# SCH_slime-vr.net
KiCad netlist of a schematic drawn in EasyEDA
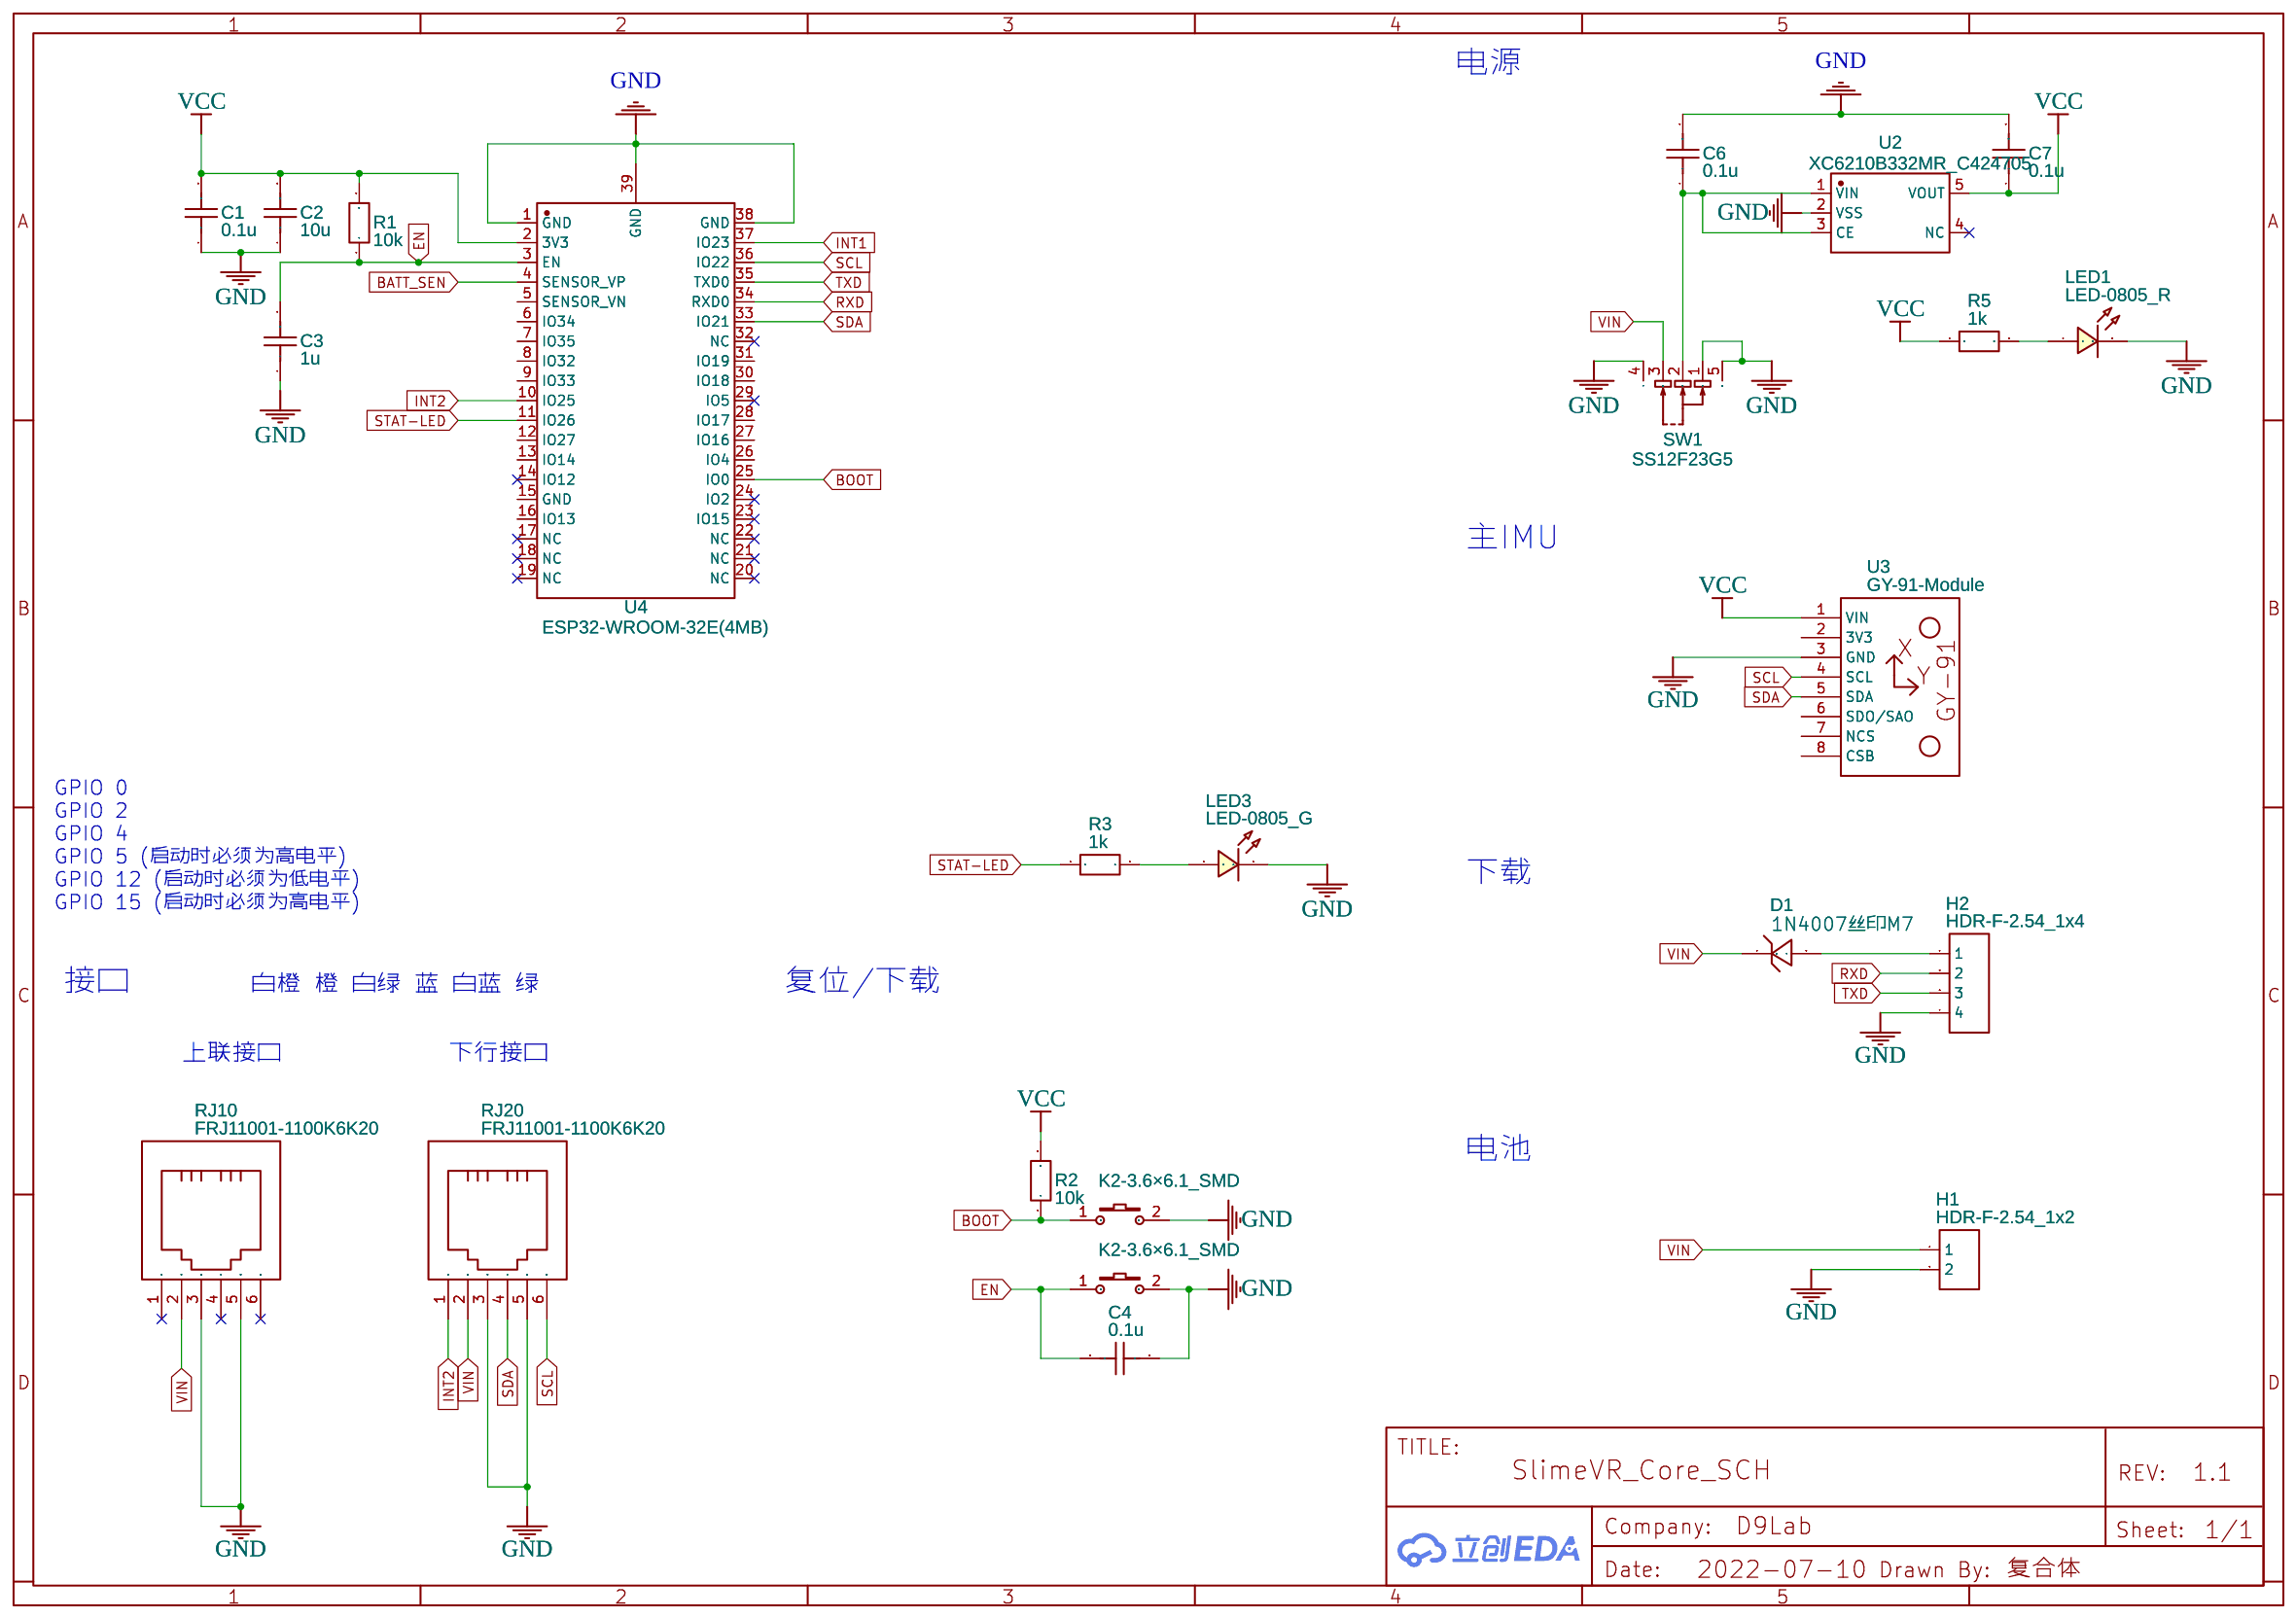
[diagram p0: SlimeVR_Core_SCH]
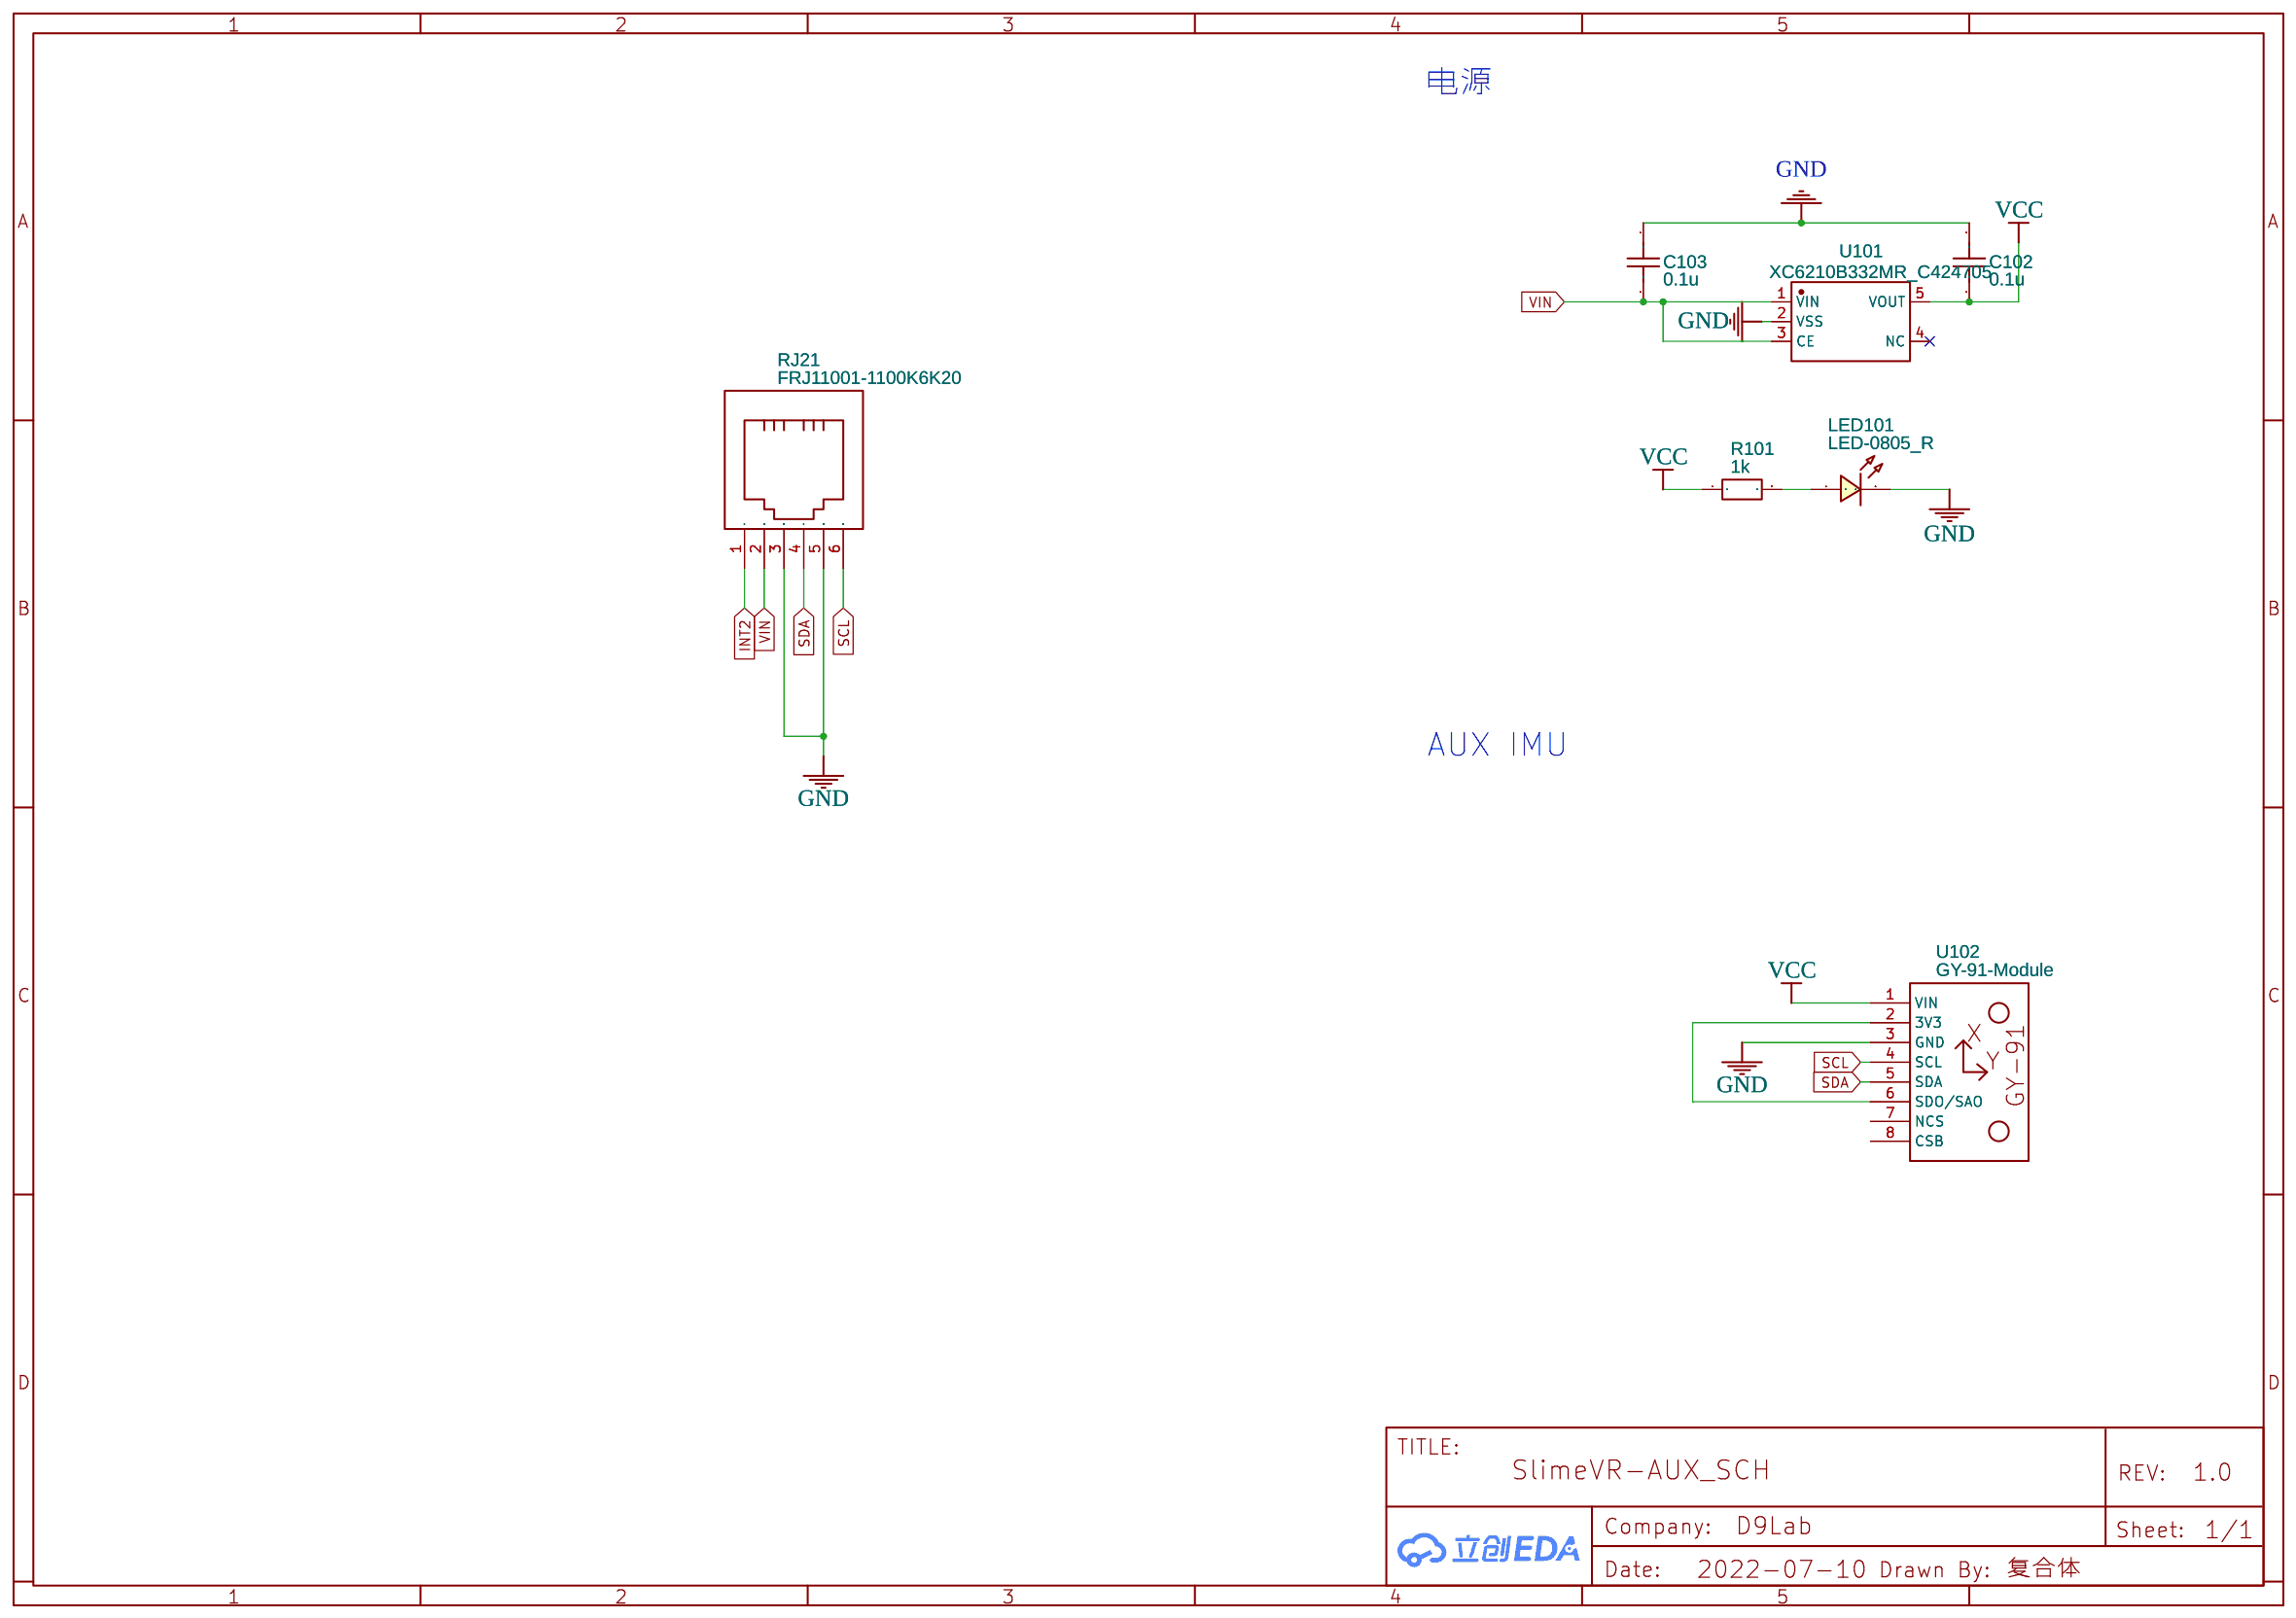
[diagram p1: SlimeVR-AUX_SCH]

(export (version "E")
  (design (tool "Eeschema 10.0.6"))
  (components
    (comp (ref "C1") (value "0.1u") (libsource (lib "") (part "C_0805_US_1")))
    (comp (ref "C2") (value "10u") (libsource (lib "") (part "C_0805_US_1")))
    (comp (ref "C3") (value "1u") (libsource (lib "") (part "C_0805_US_1")))
    (comp (ref "C4") (value "0.1u") (libsource (lib "") (part "C_0805_US")))
    (comp (ref "C6") (value "0.1u") (libsource (lib "") (part "C_0805_US_1")))
    (comp (ref "C7") (value "0.1u") (libsource (lib "") (part "C_0805_US_1")))
    (comp (ref "D1")
      (value "1N4007丝印M7")
      (fields (field (name "BOM_Supplier Part") "C9900013679"))
      (libsource (lib "") (part "1N4007丝印M7"))
    )
    (comp (ref "DL")
      (value "K2-3.6×6.1_SMD")
      (fields
        (field (name "BOM_Manufacturer Part") "K2-1107ST-A4SW-06")
        (field (name "BOM_Supplier Part") "C118141")
      )
      (libsource (lib "") (part "K2-3.6×6.1_SMD_1"))
    )
    (comp (ref "EN")
      (value "K2-3.6×6.1_SMD")
      (fields
        (field (name "BOM_Manufacturer Part") "K2-1107ST-A4SW-06")
        (field (name "BOM_Supplier Part") "C118141")
      )
      (libsource (lib "") (part "K2-3.6×6.1_SMD"))
    )
    (comp (ref "H1")
      (value "HDR-F-2.54_1x2")
      (fields (field (name "BOM_Supplier Part") "C49661"))
      (libsource (lib "") (part "HDR-F-2.54_1x2"))
    )
    (comp (ref "H2")
      (value "HDR-F-2.54_1x4")
      (fields (field (name "BOM_Supplier Part") "C225501"))
      (libsource (lib "") (part "HDR-F-2.54_1x4"))
    )
    (comp (ref "LED1")
      (value "LED-0805_R")
      (fields
        (field (name "BOM_Manufacturer Part") "17-21SURC/S530-A3/TR8")
        (field (name "BOM_Supplier Part") "C72037")
      )
      (libsource (lib "") (part "LED-0805_R"))
    )
    (comp (ref "LED3")
      (value "LED-0805_G")
      (fields (field (name "BOM_Manufacturer Part") "NCD0805G1") (field (name "BOM_Supplier Part") "C84260"))
      (libsource (lib "") (part "LED-0805_G"))
    )
    (comp (ref "R1") (value "10k") (libsource (lib "") (part "R_0805_EU")))
    (comp (ref "R2") (value "10k") (libsource (lib "") (part "R_0805_EU")))
    (comp (ref "R3") (value "1k") (libsource (lib "") (part "R_0805_EU_1")))
    (comp (ref "R5") (value "1k") (libsource (lib "") (part "R_0805_EU_1")))
    (comp (ref "RJ10")
      (value "FRJ11001-1100K6K20")
      (fields (field (name "BOM_Supplier Part") "C456393"))
      (libsource (lib "") (part "FRJ11001-1100K6K20"))
    )
    (comp (ref "RJ20")
      (value "FRJ11001-1100K6K20")
      (fields (field (name "BOM_Supplier Part") "C456393"))
      (libsource (lib "") (part "FRJ11001-1100K6K20"))
    )
    (comp (ref "SW1")
      (value "SS12F23G5")
      (fields (field (name "BOM_Supplier Part") "C2887262"))
      (libsource (lib "") (part "SS12F23G5"))
    )
    (comp (ref "U2")
      (value "XC6210B332MR_C424705")
      (fields
        (field (name "BOM_Manufacturer Part") "XC6210B332MR")
        (field (name "BOM_Supplier Part") "C424705")
      )
      (libsource (lib "") (part "XC6210B332MR_C424705"))
    )
    (comp (ref "U3")
      (value "GY-91-Module")
      (fields (field (name "BOM_Manufacturer Part") "GY-91 MPU9250 + BMP280"))
      (libsource (lib "") (part "GY-91-Module"))
    )
    (comp (ref "U4")
      (value "ESP32-WROOM-32E(4MB)")
      (fields (field (name "BOM_Supplier Part") "C701341"))
      (libsource (lib "") (part "ESP32-WROOM-32E(4MB)"))
    )
    (comp (ref "C102") (value "0.1u") (libsource (lib "") (part "C_0805_US")))
    (comp (ref "C103") (value "0.1u") (libsource (lib "") (part "C_0805_US")))
    (comp (ref "LED101")
      (value "LED-0805_R")
      (fields
        (field (name "BOM_Manufacturer Part") "17-21SURC/S530-A3/TR8")
        (field (name "BOM_Supplier Part") "C72037")
      )
      (libsource (lib "") (part "LED-0805_R"))
    )
    (comp (ref "R101") (value "1k") (libsource (lib "") (part "R_0805_EU")))
    (comp (ref "RJ21")
      (value "FRJ11001-1100K6K20")
      (fields (field (name "BOM_Supplier Part") "C456393"))
      (libsource (lib "") (part "FRJ11001-1100K6K20"))
    )
    (comp (ref "U101")
      (value "XC6210B332MR_C424705")
      (fields
        (field (name "BOM_Manufacturer Part") "XC6210B332MR")
        (field (name "BOM_Supplier Part") "C424705")
      )
      (libsource (lib "") (part "XC6210B332MR_C424705"))
    )
    (comp (ref "U102")
      (value "GY-91-Module")
      (fields (field (name "BOM_Manufacturer Part") "GY-91 MPU9250 + BMP280"))
      (libsource (lib "") (part "GY-91-Module"))
    )
  )
  (nets
    (net (code "1") (name "BATT_SEN") (class "Default")
      (node (ref "U4") (pin "4") (pinfunction "SENSOR_VP_4") (pintype "unspecified"))
    )
    (net (code "2") (name "BOOT") (class "Default")
      (node (ref "DL") (pin "1") (pinfunction "1_1") (pintype "unspecified"))
      (node (ref "R2") (pin "1") (pinfunction "1_1") (pintype "unspecified"))
      (node (ref "U4") (pin "25") (pinfunction "IO0_25") (pintype "unspecified"))
    )
    (net (code "3") (name "EN") (class "Default")
      (node (ref "C3") (pin "2") (pinfunction "2_2") (pintype "unspecified"))
      (node (ref "C4") (pin "2") (pinfunction "2_2") (pintype "unspecified"))
      (node (ref "EN") (pin "1") (pinfunction "1_1") (pintype "unspecified"))
      (node (ref "R1") (pin "1") (pinfunction "1_1") (pintype "unspecified"))
      (node (ref "U4") (pin "3") (pinfunction "EN_3") (pintype "unspecified"))
    )
    (net (code "4") (name "GND") (class "Default")
      (node (ref "C1") (pin "1") (pinfunction "1_1") (pintype "unspecified"))
      (node (ref "C102") (pin "2") (pinfunction "2_2") (pintype "unspecified"))
      (node (ref "C103") (pin "2") (pinfunction "2_2") (pintype "unspecified"))
      (node (ref "C2") (pin "1") (pinfunction "1_1") (pintype "unspecified"))
      (node (ref "C3") (pin "1") (pinfunction "1_1") (pintype "unspecified"))
      (node (ref "C4") (pin "1") (pinfunction "1_1") (pintype "unspecified"))
      (node (ref "C6") (pin "2") (pinfunction "2_2") (pintype "unspecified"))
      (node (ref "C7") (pin "2") (pinfunction "2_2") (pintype "unspecified"))
      (node (ref "DL") (pin "2") (pinfunction "2_2") (pintype "unspecified"))
      (node (ref "EN") (pin "2") (pinfunction "2_2") (pintype "unspecified"))
      (node (ref "H1") (pin "2") (pinfunction "2_2") (pintype "input"))
      (node (ref "H2") (pin "4") (pinfunction "4_4") (pintype "unspecified"))
      (node (ref "LED1") (pin "2") (pinfunction "2_2") (pintype "unspecified"))
      (node (ref "LED101") (pin "2") (pinfunction "2_2") (pintype "unspecified"))
      (node (ref "LED3") (pin "2") (pinfunction "2_2") (pintype "unspecified"))
      (node (ref "RJ10") (pin "3") (pinfunction "3_3") (pintype "unspecified"))
      (node (ref "RJ10") (pin "5") (pinfunction "5_5") (pintype "unspecified"))
      (node (ref "RJ20") (pin "3") (pinfunction "3_3") (pintype "unspecified"))
      (node (ref "RJ20") (pin "5") (pinfunction "5_5") (pintype "unspecified"))
      (node (ref "RJ21") (pin "3") (pinfunction "3_3") (pintype "unspecified"))
      (node (ref "RJ21") (pin "5") (pinfunction "5_5") (pintype "unspecified"))
      (node (ref "SW1") (pin "1") (pinfunction "1_1") (pintype "unspecified"))
      (node (ref "SW1") (pin "4") (pinfunction "4_4") (pintype "unspecified"))
      (node (ref "SW1") (pin "5") (pinfunction "5_5") (pintype "unspecified"))
      (node (ref "U101") (pin "2") (pinfunction "VSS_2") (pintype "unspecified"))
      (node (ref "U102") (pin "3") (pinfunction "GND_3") (pintype "unspecified"))
      (node (ref "U2") (pin "2") (pinfunction "VSS_2") (pintype "unspecified"))
      (node (ref "U3") (pin "3") (pinfunction "GND_3") (pintype "unspecified"))
      (node (ref "U4") (pin "1") (pinfunction "GND_1") (pintype "unspecified"))
      (node (ref "U4") (pin "38") (pinfunction "GND_38") (pintype "unspecified"))
      (node (ref "U4") (pin "39") (pinfunction "GND_39") (pintype "unspecified"))
    )
    (net (code "5") (name "INT1") (class "Default")
      (node (ref "U4") (pin "37") (pinfunction "IO23_37") (pintype "unspecified"))
    )
    (net (code "6") (name "INT2") (class "Default")
      (node (ref "RJ20") (pin "1") (pinfunction "1_1") (pintype "unspecified"))
      (node (ref "RJ21") (pin "1") (pinfunction "1_1") (pintype "unspecified"))
      (node (ref "U4") (pin "10") (pinfunction "IO25_10") (pintype "unspecified"))
    )
    (net (code "7") (name "Net-(D1-A)") (class "Default")
      (node (ref "D1") (pin "2") (pinfunction "A_2") (pintype "unspecified"))
      (node (ref "H2") (pin "1") (pinfunction "1_1") (pintype "unspecified"))
    )
    (net (code "8") (name "Net-(LED1-Pad1)") (class "Default")
      (node (ref "LED1") (pin "1") (pinfunction "1_1") (pintype "unspecified"))
      (node (ref "R5") (pin "2") (pinfunction "2_2") (pintype "unspecified"))
    )
    (net (code "9") (name "Net-(LED3-Pad1)") (class "Default")
      (node (ref "LED3") (pin "1") (pinfunction "1_1") (pintype "unspecified"))
      (node (ref "R3") (pin "2") (pinfunction "2_2") (pintype "unspecified"))
    )
    (net (code "10") (name "Net-(LED101-Pad1)") (class "Default")
      (node (ref "LED101") (pin "1") (pinfunction "1_1") (pintype "unspecified"))
      (node (ref "R101") (pin "2") (pinfunction "2_2") (pintype "unspecified"))
    )
    (net (code "11") (name "Net-(U2-CE)") (class "Default")
      (node (ref "C6") (pin "1") (pinfunction "1_1") (pintype "unspecified"))
      (node (ref "SW1") (pin "2") (pinfunction "2_2") (pintype "unspecified"))
      (node (ref "U2") (pin "1") (pinfunction "VIN_1") (pintype "unspecified"))
      (node (ref "U2") (pin "3") (pinfunction "CE_3") (pintype "unspecified"))
    )
    (net (code "12") (name "Net-(U102-3V3)") (class "Default")
      (node (ref "U102") (pin "2") (pinfunction "3V3_2") (pintype "unspecified"))
      (node (ref "U102") (pin "6") (pinfunction "SDO/SAO_6") (pintype "unspecified"))
    )
    (net (code "13") (name "RXD") (class "Default")
      (node (ref "H2") (pin "2") (pinfunction "2_2") (pintype "unspecified"))
      (node (ref "U4") (pin "34") (pinfunction "RXD0_34") (pintype "unspecified"))
    )
    (net (code "14") (name "SCL") (class "Default")
      (node (ref "RJ20") (pin "6") (pinfunction "6_6") (pintype "unspecified"))
      (node (ref "RJ21") (pin "6") (pinfunction "6_6") (pintype "unspecified"))
      (node (ref "U102") (pin "4") (pinfunction "SCL_4") (pintype "unspecified"))
      (node (ref "U3") (pin "4") (pinfunction "SCL_4") (pintype "unspecified"))
      (node (ref "U4") (pin "36") (pinfunction "IO22_36") (pintype "unspecified"))
    )
    (net (code "15") (name "SDA") (class "Default")
      (node (ref "RJ20") (pin "4") (pinfunction "4_4") (pintype "unspecified"))
      (node (ref "RJ21") (pin "4") (pinfunction "4_4") (pintype "unspecified"))
      (node (ref "U102") (pin "5") (pinfunction "SDA_5") (pintype "unspecified"))
      (node (ref "U3") (pin "5") (pinfunction "SDA_5") (pintype "unspecified"))
      (node (ref "U4") (pin "33") (pinfunction "IO21_33") (pintype "unspecified"))
    )
    (net (code "16") (name "STAT-LED") (class "Default")
      (node (ref "R3") (pin "1") (pinfunction "1_1") (pintype "unspecified"))
      (node (ref "U4") (pin "11") (pinfunction "IO26_11") (pintype "unspecified"))
    )
    (net (code "17") (name "TXD") (class "Default")
      (node (ref "H2") (pin "3") (pinfunction "3_3") (pintype "unspecified"))
      (node (ref "U4") (pin "35") (pinfunction "TXD0_35") (pintype "unspecified"))
    )
    (net (code "18") (name "VCC") (class "Default")
      (node (ref "C1") (pin "2") (pinfunction "2_2") (pintype "unspecified"))
      (node (ref "C102") (pin "1") (pinfunction "1_1") (pintype "unspecified"))
      (node (ref "C2") (pin "2") (pinfunction "2_2") (pintype "unspecified"))
      (node (ref "C7") (pin "1") (pinfunction "1_1") (pintype "unspecified"))
      (node (ref "R1") (pin "2") (pinfunction "2_2") (pintype "unspecified"))
      (node (ref "R101") (pin "1") (pinfunction "1_1") (pintype "unspecified"))
      (node (ref "R2") (pin "2") (pinfunction "2_2") (pintype "unspecified"))
      (node (ref "R5") (pin "1") (pinfunction "1_1") (pintype "unspecified"))
      (node (ref "U101") (pin "5") (pinfunction "VOUT_5") (pintype "unspecified"))
      (node (ref "U102") (pin "1") (pinfunction "VIN_1") (pintype "unspecified"))
      (node (ref "U2") (pin "5") (pinfunction "VOUT_5") (pintype "unspecified"))
      (node (ref "U3") (pin "1") (pinfunction "VIN_1") (pintype "unspecified"))
      (node (ref "U4") (pin "2") (pinfunction "3V3_2") (pintype "unspecified"))
    )
    (net (code "19") (name "VIN") (class "Default")
      (node (ref "C103") (pin "1") (pinfunction "1_1") (pintype "unspecified"))
      (node (ref "D1") (pin "1") (pinfunction "C_1") (pintype "unspecified"))
      (node (ref "H1") (pin "1") (pinfunction "1_1") (pintype "input"))
      (node (ref "RJ10") (pin "2") (pinfunction "2_2") (pintype "unspecified"))
      (node (ref "RJ20") (pin "2") (pinfunction "2_2") (pintype "unspecified"))
      (node (ref "RJ21") (pin "2") (pinfunction "2_2") (pintype "unspecified"))
      (node (ref "SW1") (pin "3") (pinfunction "3_3") (pintype "unspecified"))
      (node (ref "U101") (pin "1") (pinfunction "VIN_1") (pintype "unspecified"))
      (node (ref "U101") (pin "3") (pinfunction "CE_3") (pintype "unspecified"))
    )
    (net (code "20") (name "unconnected-(RJ10-Pad1)") (class "Default")
      (node (ref "RJ10") (pin "1") (pinfunction "1_1") (pintype "unspecified+no_connect"))
    )
    (net (code "21") (name "unconnected-(RJ10-Pad4)") (class "Default")
      (node (ref "RJ10") (pin "4") (pinfunction "4_4") (pintype "unspecified+no_connect"))
    )
    (net (code "22") (name "unconnected-(RJ10-Pad6)") (class "Default")
      (node (ref "RJ10") (pin "6") (pinfunction "6_6") (pintype "unspecified+no_connect"))
    )
    (net (code "23") (name "unconnected-(U2-NC-Pad4)") (class "Default")
      (node (ref "U2") (pin "4") (pinfunction "NC_4") (pintype "unspecified+no_connect"))
    )
    (net (code "24") (name "unconnected-(U3-3V3-Pad2)") (class "Default")
      (node (ref "U3") (pin "2") (pinfunction "3V3_2") (pintype "unspecified"))
    )
    (net (code "25") (name "unconnected-(U3-CSB-Pad8)") (class "Default")
      (node (ref "U3") (pin "8") (pinfunction "CSB_8") (pintype "unspecified"))
    )
    (net (code "26") (name "unconnected-(U3-NCS-Pad7)") (class "Default")
      (node (ref "U3") (pin "7") (pinfunction "NCS_7") (pintype "unspecified"))
    )
    (net (code "27") (name "unconnected-(U3-SDO{slash}SAO-Pad6)") (class "Default")
      (node (ref "U3") (pin "6") (pinfunction "SDO/SAO_6") (pintype "unspecified"))
    )
    (net (code "28") (name "unconnected-(U4-GND-Pad15)") (class "Default")
      (node (ref "U4") (pin "15") (pinfunction "GND_15") (pintype "unspecified"))
    )
    (net (code "29") (name "unconnected-(U4-IO2-Pad24)") (class "Default")
      (node (ref "U4") (pin "24") (pinfunction "IO2_24") (pintype "unspecified+no_connect"))
    )
    (net (code "30") (name "unconnected-(U4-IO4-Pad26)") (class "Default")
      (node (ref "U4") (pin "26") (pinfunction "IO4_26") (pintype "unspecified"))
    )
    (net (code "31") (name "unconnected-(U4-IO5-Pad29)") (class "Default")
      (node (ref "U4") (pin "29") (pinfunction "IO5_29") (pintype "unspecified+no_connect"))
    )
    (net (code "32") (name "unconnected-(U4-IO12-Pad14)") (class "Default")
      (node (ref "U4") (pin "14") (pinfunction "IO12_14") (pintype "unspecified+no_connect"))
    )
    (net (code "33") (name "unconnected-(U4-IO13-Pad16)") (class "Default")
      (node (ref "U4") (pin "16") (pinfunction "IO13_16") (pintype "unspecified"))
    )
    (net (code "34") (name "unconnected-(U4-IO14-Pad13)") (class "Default")
      (node (ref "U4") (pin "13") (pinfunction "IO14_13") (pintype "unspecified"))
    )
    (net (code "35") (name "unconnected-(U4-IO15-Pad23)") (class "Default")
      (node (ref "U4") (pin "23") (pinfunction "IO15_23") (pintype "unspecified+no_connect"))
    )
    (net (code "36") (name "unconnected-(U4-IO16-Pad27)") (class "Default")
      (node (ref "U4") (pin "27") (pinfunction "IO16_27") (pintype "unspecified"))
    )
    (net (code "37") (name "unconnected-(U4-IO17-Pad28)") (class "Default")
      (node (ref "U4") (pin "28") (pinfunction "IO17_28") (pintype "unspecified"))
    )
    (net (code "38") (name "unconnected-(U4-IO18-Pad30)") (class "Default")
      (node (ref "U4") (pin "30") (pinfunction "IO18_30") (pintype "unspecified"))
    )
    (net (code "39") (name "unconnected-(U4-IO19-Pad31)") (class "Default")
      (node (ref "U4") (pin "31") (pinfunction "IO19_31") (pintype "unspecified"))
    )
    (net (code "40") (name "unconnected-(U4-IO27-Pad12)") (class "Default")
      (node (ref "U4") (pin "12") (pinfunction "IO27_12") (pintype "unspecified"))
    )
    (net (code "41") (name "unconnected-(U4-IO32-Pad8)") (class "Default")
      (node (ref "U4") (pin "8") (pinfunction "IO32_8") (pintype "unspecified"))
    )
    (net (code "42") (name "unconnected-(U4-IO33-Pad9)") (class "Default")
      (node (ref "U4") (pin "9") (pinfunction "IO33_9") (pintype "unspecified"))
    )
    (net (code "43") (name "unconnected-(U4-IO34-Pad6)") (class "Default")
      (node (ref "U4") (pin "6") (pinfunction "IO34_6") (pintype "unspecified"))
    )
    (net (code "44") (name "unconnected-(U4-IO35-Pad7)") (class "Default")
      (node (ref "U4") (pin "7") (pinfunction "IO35_7") (pintype "unspecified"))
    )
    (net (code "45") (name "unconnected-(U4-NC-Pad17)") (class "Default")
      (node (ref "U4") (pin "17") (pinfunction "NC_17") (pintype "unspecified+no_connect"))
    )
    (net (code "46") (name "unconnected-(U4-NC-Pad18)") (class "Default")
      (node (ref "U4") (pin "18") (pinfunction "NC_18") (pintype "unspecified+no_connect"))
    )
    (net (code "47") (name "unconnected-(U4-NC-Pad19)") (class "Default")
      (node (ref "U4") (pin "19") (pinfunction "NC_19") (pintype "unspecified+no_connect"))
    )
    (net (code "48") (name "unconnected-(U4-NC-Pad20)") (class "Default")
      (node (ref "U4") (pin "20") (pinfunction "NC_20") (pintype "unspecified+no_connect"))
    )
    (net (code "49") (name "unconnected-(U4-NC-Pad21)") (class "Default")
      (node (ref "U4") (pin "21") (pinfunction "NC_21") (pintype "unspecified+no_connect"))
    )
    (net (code "50") (name "unconnected-(U4-NC-Pad22)") (class "Default")
      (node (ref "U4") (pin "22") (pinfunction "NC_22") (pintype "unspecified+no_connect"))
    )
    (net (code "51") (name "unconnected-(U4-NC-Pad32)") (class "Default")
      (node (ref "U4") (pin "32") (pinfunction "NC_32") (pintype "unspecified+no_connect"))
    )
    (net (code "52") (name "unconnected-(U4-SENSOR_VN-Pad5)") (class "Default")
      (node (ref "U4") (pin "5") (pinfunction "SENSOR_VN_5") (pintype "unspecified"))
    )
    (net (code "53") (name "unconnected-(U101-NC-Pad4)") (class "Default")
      (node (ref "U101") (pin "4") (pinfunction "NC_4") (pintype "unspecified+no_connect"))
    )
    (net (code "54") (name "unconnected-(U102-CSB-Pad8)") (class "Default")
      (node (ref "U102") (pin "8") (pinfunction "CSB_8") (pintype "unspecified"))
    )
    (net (code "55") (name "unconnected-(U102-NCS-Pad7)") (class "Default")
      (node (ref "U102") (pin "7") (pinfunction "NCS_7") (pintype "unspecified"))
    )
  )
)
